# Schematic1.net
KiCad netlist of a schematic drawn in Altium Designer
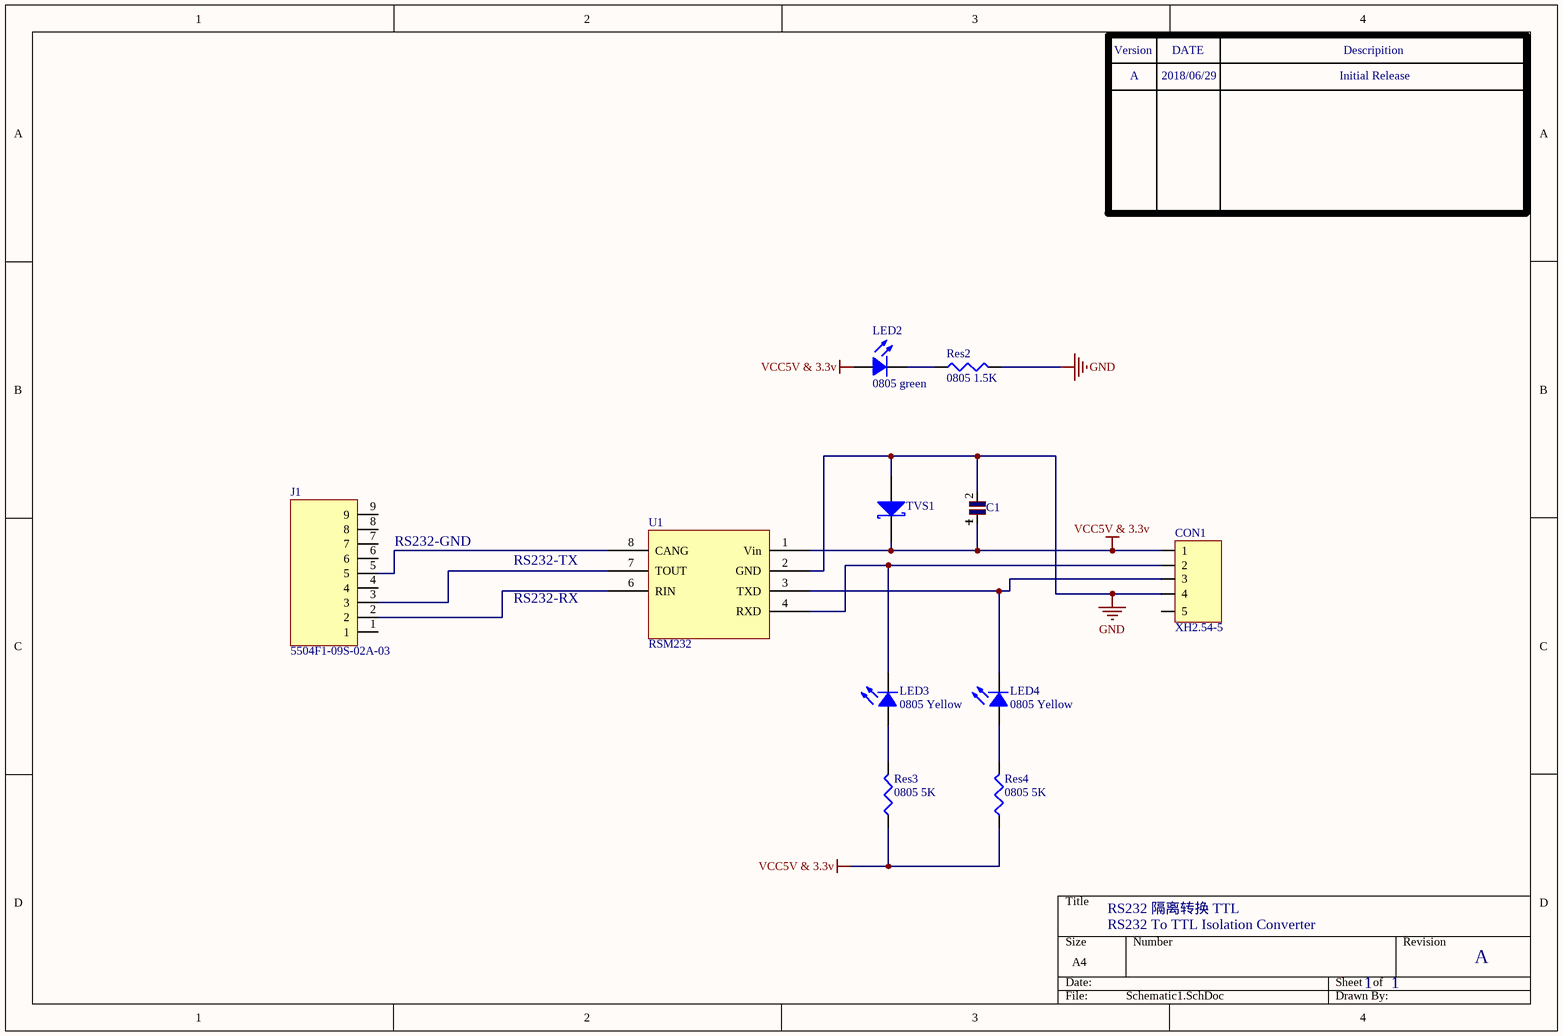
[diagram p0: Schematic1.SchDoc]

(export (version "E")
  (design (tool "Eeschema 10.0.6"))
  (components
    (comp (ref "C1")
      (value "T491C226K025AT")
      (footprint "T491C226K010AT")
      (description "表面贴装钽电容, 22 μF, 10 V, T491 系列, ± 10%, 2312 [6032 公")
      (libsource (lib "FUWEIZHANG") (part "T491C226K010AT"))
    )
    (comp (ref "CON1")
      (value "XH2.54-5")
      (footprint "XH2.54-5")
      (libsource (lib "FUWEIZHANG") (part "XH2.54-5"))
    )
    (comp (ref "J1")
      (value "5504F1-09S-02A-03")
      (footprint "5504F1-09S-02A-03")
      (description "D-Sub 连接器, 9 触点, 插座, DE, AMPLIMITE HD-20系列, 金属主体, 焊接")
      (libsource (lib "FUWEIZHANG") (part "5504F1-09S-02A-03"))
    )
    (comp (ref "LED2")
      (value "0805 green")
      (footprint "0805 LED")
      (libsource (lib "FUWEIZHANG") (part "0805 LED"))
    )
    (comp (ref "LED3")
      (value "0805 Yellow")
      (footprint "0805 LED")
      (libsource (lib "FUWEIZHANG") (part "0805 LED"))
    )
    (comp (ref "LED4")
      (value "0805 Yellow")
      (footprint "0805 LED")
      (libsource (lib "FUWEIZHANG") (part "0805 LED"))
    )
    (comp (ref "Res2")
      (value "0805 1.5K")
      (footprint "0805 Resistor")
      (libsource (lib "FUWEIZHANG") (part "0805 Resistor"))
    )
    (comp (ref "Res3")
      (value "0805 5K")
      (footprint "0805 Resistor")
      (libsource (lib "FUWEIZHANG") (part "0805 Resistor"))
    )
    (comp (ref "Res4")
      (value "0805 5K")
      (footprint "0805 Resistor")
      (libsource (lib "FUWEIZHANG") (part "0805 Resistor"))
    )
    (comp (ref "TVS1")
      (value "SMBJ5.0A")
      (footprint "SMBJ5.0A")
      (description "ESD 抑制器/TVS 二极管")
      (libsource (lib "FUWEIZHANG") (part "SMBJ5.0A"))
    )
    (comp (ref "U1") (value "RSM232") (footprint "RSM232") (libsource (lib "ZY-power") (part "RSM232")))
  )
  (nets
    (net (code "1") (name "GND") (class "Default")
      (node (ref "C1") (pin "2") (pinfunction "2_2") (pintype "passive"))
      (node (ref "CON1") (pin "4") (pinfunction "4_4") (pintype "passive"))
      (node (ref "Res2") (pin "2") (pinfunction "2_2") (pintype "passive"))
      (node (ref "TVS1") (pin "1") (pinfunction "A_1") (pintype "passive"))
      (node (ref "U1") (pin "2") (pinfunction "GND_2") (pintype "passive"))
    )
    (net (code "2") (name "Net-(LED2-K)") (class "Default")
      (node (ref "LED2") (pin "2") (pinfunction "K_2") (pintype "passive"))
      (node (ref "Res2") (pin "1") (pinfunction "1_1") (pintype "passive"))
    )
    (net (code "3") (name "Net-(LED3-A)") (class "Default")
      (node (ref "LED3") (pin "1") (pinfunction "A_1") (pintype "passive"))
      (node (ref "Res3") (pin "2") (pinfunction "2_2") (pintype "passive"))
    )
    (net (code "4") (name "Net-(LED3-K)") (class "Default")
      (node (ref "CON1") (pin "2") (pinfunction "2_2") (pintype "passive"))
      (node (ref "LED3") (pin "2") (pinfunction "K_2") (pintype "passive"))
      (node (ref "U1") (pin "4") (pinfunction "RXD_4") (pintype "passive"))
    )
    (net (code "5") (name "Net-(LED4-A)") (class "Default")
      (node (ref "LED4") (pin "1") (pinfunction "A_1") (pintype "passive"))
      (node (ref "Res4") (pin "2") (pinfunction "2_2") (pintype "passive"))
    )
    (net (code "6") (name "Net-(LED4-K)") (class "Default")
      (node (ref "CON1") (pin "3") (pinfunction "3_3") (pintype "passive"))
      (node (ref "LED4") (pin "2") (pinfunction "K_2") (pintype "passive"))
      (node (ref "U1") (pin "3") (pinfunction "TXD_3") (pintype "passive"))
    )
    (net (code "7") (name "Net-(U1-CANG)") (class "Default")
      (node (ref "J1") (pin "5") (pinfunction "5_5") (pintype "passive"))
      (node (ref "U1") (pin "8") (pinfunction "CANG_8") (pintype "passive"))
    )
    (net (code "8") (name "Net-(U1-RIN)") (class "Default")
      (node (ref "J1") (pin "2") (pinfunction "2_2") (pintype "passive"))
      (node (ref "U1") (pin "6") (pinfunction "RIN_6") (pintype "passive"))
    )
    (net (code "9") (name "Net-(U1-TOUT)") (class "Default")
      (node (ref "J1") (pin "3") (pinfunction "3_3") (pintype "passive"))
      (node (ref "U1") (pin "7") (pinfunction "TOUT_7") (pintype "passive"))
    )
    (net (code "10") (name "VCC5V & 3.3v") (class "Default")
      (node (ref "C1") (pin "1") (pinfunction "1_1") (pintype "passive"))
      (node (ref "CON1") (pin "1") (pinfunction "1_1") (pintype "passive"))
      (node (ref "LED2") (pin "1") (pinfunction "A_1") (pintype "passive"))
      (node (ref "Res3") (pin "1") (pinfunction "1_1") (pintype "passive"))
      (node (ref "Res4") (pin "1") (pinfunction "1_1") (pintype "passive"))
      (node (ref "TVS1") (pin "2") (pinfunction "K_2") (pintype "passive"))
      (node (ref "U1") (pin "1") (pinfunction "Vin_1") (pintype "passive"))
    )
    (net (code "11") (name "unconnected-(CON1-Pad5)") (class "Default")
      (node (ref "CON1") (pin "5") (pinfunction "5_5") (pintype "passive"))
    )
    (net (code "12") (name "unconnected-(J1-Pad1)") (class "Default")
      (node (ref "J1") (pin "1") (pinfunction "1_1") (pintype "passive"))
    )
    (net (code "13") (name "unconnected-(J1-Pad4)") (class "Default")
      (node (ref "J1") (pin "4") (pinfunction "4_4") (pintype "passive"))
    )
    (net (code "14") (name "unconnected-(J1-Pad6)") (class "Default")
      (node (ref "J1") (pin "6") (pinfunction "6_6") (pintype "passive"))
    )
    (net (code "15") (name "unconnected-(J1-Pad7)") (class "Default")
      (node (ref "J1") (pin "7") (pinfunction "7_7") (pintype "passive"))
    )
    (net (code "16") (name "unconnected-(J1-Pad8)") (class "Default")
      (node (ref "J1") (pin "8") (pinfunction "8_8") (pintype "passive"))
    )
    (net (code "17") (name "unconnected-(J1-Pad9)") (class "Default")
      (node (ref "J1") (pin "9") (pinfunction "9_9") (pintype "passive"))
    )
  )
)
